# IR80-250GF.net
KiCad netlist of a schematic drawn in Altium Designer
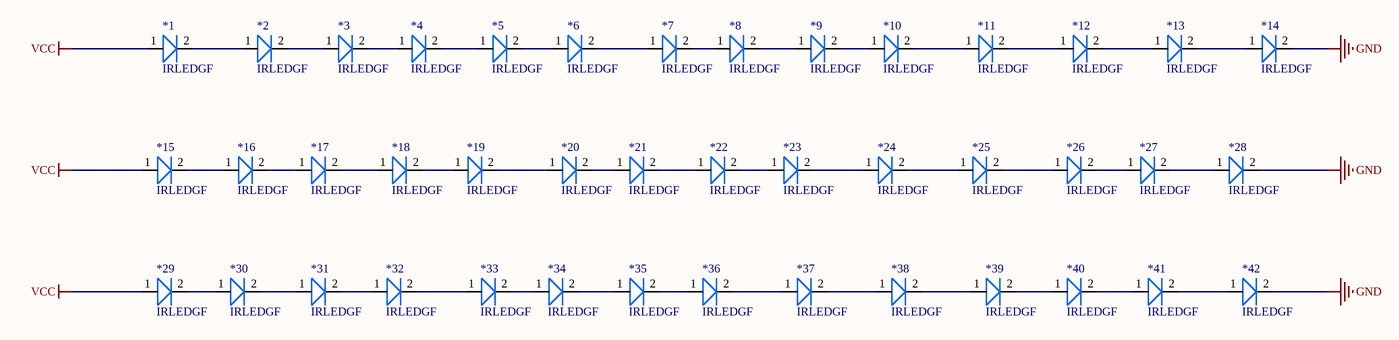
[diagram p0: IR80-250GF.SchDoc]

(export (version "E")
  (design (tool "Eeschema 10.0.6"))
  (components
    (comp (ref "*1")
      (value "IRLEDGF")
      (footprint "LED:LED 1W/3W")
      (libsource (lib "mySchLib") (part "IRLEDGF"))
    )
    (comp (ref "*2")
      (value "IRLEDGF")
      (footprint "LED:LED 1W/3W")
      (libsource (lib "mySchLib") (part "IRLEDGF"))
    )
    (comp (ref "*3")
      (value "IRLEDGF")
      (footprint "LED:LED 1W/3W")
      (libsource (lib "mySchLib") (part "IRLEDGF"))
    )
    (comp (ref "*4")
      (value "IRLEDGF")
      (footprint "LED:LED 1W/3W")
      (libsource (lib "mySchLib") (part "IRLEDGF"))
    )
    (comp (ref "*5")
      (value "IRLEDGF")
      (footprint "LED:LED 1W/3W")
      (libsource (lib "mySchLib") (part "IRLEDGF"))
    )
    (comp (ref "*6")
      (value "IRLEDGF")
      (footprint "LED:LED 1W/3W")
      (libsource (lib "mySchLib") (part "IRLEDGF"))
    )
    (comp (ref "*7")
      (value "IRLEDGF")
      (footprint "LED:LED 1W/3W")
      (libsource (lib "mySchLib") (part "IRLEDGF"))
    )
    (comp (ref "*8")
      (value "IRLEDGF")
      (footprint "LED:LED 1W/3W")
      (libsource (lib "mySchLib") (part "IRLEDGF"))
    )
    (comp (ref "*9")
      (value "IRLEDGF")
      (footprint "LED:LED 1W/3W")
      (libsource (lib "mySchLib") (part "IRLEDGF"))
    )
    (comp (ref "*10")
      (value "IRLEDGF")
      (footprint "LED:LED 1W/3W")
      (libsource (lib "mySchLib") (part "IRLEDGF"))
    )
    (comp (ref "*11")
      (value "IRLEDGF")
      (footprint "LED:LED 1W/3W")
      (libsource (lib "mySchLib") (part "IRLEDGF"))
    )
    (comp (ref "*12")
      (value "IRLEDGF")
      (footprint "LED:LED 1W/3W")
      (libsource (lib "mySchLib") (part "IRLEDGF"))
    )
    (comp (ref "*13")
      (value "IRLEDGF")
      (footprint "LED:LED 1W/3W")
      (libsource (lib "mySchLib") (part "IRLEDGF"))
    )
    (comp (ref "*14")
      (value "IRLEDGF")
      (footprint "LED:LED 1W/3W")
      (libsource (lib "mySchLib") (part "IRLEDGF"))
    )
    (comp (ref "*15")
      (value "IRLEDGF")
      (footprint "LED:LED 1W/3W")
      (libsource (lib "mySchLib") (part "IRLEDGF"))
    )
    (comp (ref "*16")
      (value "IRLEDGF")
      (footprint "LED:LED 1W/3W")
      (libsource (lib "mySchLib") (part "IRLEDGF"))
    )
    (comp (ref "*17")
      (value "IRLEDGF")
      (footprint "LED:LED 1W/3W")
      (libsource (lib "mySchLib") (part "IRLEDGF"))
    )
    (comp (ref "*18")
      (value "IRLEDGF")
      (footprint "LED:LED 1W/3W")
      (libsource (lib "mySchLib") (part "IRLEDGF"))
    )
    (comp (ref "*19")
      (value "IRLEDGF")
      (footprint "LED:LED 1W/3W")
      (libsource (lib "mySchLib") (part "IRLEDGF"))
    )
    (comp (ref "*20")
      (value "IRLEDGF")
      (footprint "LED:LED 1W/3W")
      (libsource (lib "mySchLib") (part "IRLEDGF"))
    )
    (comp (ref "*21")
      (value "IRLEDGF")
      (footprint "LED:LED 1W/3W")
      (libsource (lib "mySchLib") (part "IRLEDGF"))
    )
    (comp (ref "*22")
      (value "IRLEDGF")
      (footprint "LED:LED 1W/3W")
      (libsource (lib "mySchLib") (part "IRLEDGF"))
    )
    (comp (ref "*23")
      (value "IRLEDGF")
      (footprint "LED:LED 1W/3W")
      (libsource (lib "mySchLib") (part "IRLEDGF"))
    )
    (comp (ref "*24")
      (value "IRLEDGF")
      (footprint "LED:LED 1W/3W")
      (libsource (lib "mySchLib") (part "IRLEDGF"))
    )
    (comp (ref "*25")
      (value "IRLEDGF")
      (footprint "LED:LED 1W/3W")
      (libsource (lib "mySchLib") (part "IRLEDGF"))
    )
    (comp (ref "*26")
      (value "IRLEDGF")
      (footprint "LED:LED 1W/3W")
      (libsource (lib "mySchLib") (part "IRLEDGF"))
    )
    (comp (ref "*27")
      (value "IRLEDGF")
      (footprint "LED:LED 1W/3W")
      (libsource (lib "mySchLib") (part "IRLEDGF"))
    )
    (comp (ref "*28")
      (value "IRLEDGF")
      (footprint "LED:LED 1W/3W")
      (libsource (lib "mySchLib") (part "IRLEDGF"))
    )
    (comp (ref "*29")
      (value "IRLEDGF")
      (footprint "LED:LED 1W/3W")
      (libsource (lib "mySchLib") (part "IRLEDGF"))
    )
    (comp (ref "*30")
      (value "IRLEDGF")
      (footprint "LED:LED 1W/3W")
      (libsource (lib "mySchLib") (part "IRLEDGF"))
    )
    (comp (ref "*31")
      (value "IRLEDGF")
      (footprint "LED:LED 1W/3W")
      (libsource (lib "mySchLib") (part "IRLEDGF"))
    )
    (comp (ref "*32")
      (value "IRLEDGF")
      (footprint "LED:LED 1W/3W")
      (libsource (lib "mySchLib") (part "IRLEDGF"))
    )
    (comp (ref "*33")
      (value "IRLEDGF")
      (footprint "LED:LED 1W/3W")
      (libsource (lib "mySchLib") (part "IRLEDGF"))
    )
    (comp (ref "*34")
      (value "IRLEDGF")
      (footprint "LED:LED 1W/3W")
      (libsource (lib "mySchLib") (part "IRLEDGF"))
    )
    (comp (ref "*35")
      (value "IRLEDGF")
      (footprint "LED:LED 1W/3W")
      (libsource (lib "mySchLib") (part "IRLEDGF"))
    )
    (comp (ref "*36")
      (value "IRLEDGF")
      (footprint "LED:LED 1W/3W")
      (libsource (lib "mySchLib") (part "IRLEDGF"))
    )
    (comp (ref "*37")
      (value "IRLEDGF")
      (footprint "LED:LED 1W/3W")
      (libsource (lib "mySchLib") (part "IRLEDGF"))
    )
    (comp (ref "*38")
      (value "IRLEDGF")
      (footprint "LED:LED 1W/3W")
      (libsource (lib "mySchLib") (part "IRLEDGF"))
    )
    (comp (ref "*39")
      (value "IRLEDGF")
      (footprint "LED:LED 1W/3W")
      (libsource (lib "mySchLib") (part "IRLEDGF"))
    )
    (comp (ref "*40")
      (value "IRLEDGF")
      (footprint "LED:LED 1W/3W")
      (libsource (lib "mySchLib") (part "IRLEDGF"))
    )
    (comp (ref "*41")
      (value "IRLEDGF")
      (footprint "LED:LED 1W/3W")
      (libsource (lib "mySchLib") (part "IRLEDGF"))
    )
    (comp (ref "*42")
      (value "IRLEDGF")
      (footprint "LED:LED 1W/3W")
      (libsource (lib "mySchLib") (part "IRLEDGF"))
    )
  )
  (nets
    (net (code "1") (name "GND") (class "Default")
      (node (ref "*14") (pin "2") (pinfunction "-_2") (pintype "open_collector"))
      (node (ref "*28") (pin "2") (pinfunction "-_2") (pintype "open_collector"))
      (node (ref "*42") (pin "2") (pinfunction "-_2") (pintype "open_collector"))
    )
    (net (code "2") (name "Net-(*1--)") (class "Default")
      (node (ref "*1") (pin "2") (pinfunction "-_2") (pintype "open_collector"))
      (node (ref "*2") (pin "1") (pinfunction "+_1") (pintype "passive"))
    )
    (net (code "3") (name "Net-(*2--)") (class "Default")
      (node (ref "*2") (pin "2") (pinfunction "-_2") (pintype "open_collector"))
      (node (ref "*3") (pin "1") (pinfunction "+_1") (pintype "passive"))
    )
    (net (code "4") (name "Net-(*3--)") (class "Default")
      (node (ref "*3") (pin "2") (pinfunction "-_2") (pintype "open_collector"))
      (node (ref "*4") (pin "1") (pinfunction "+_1") (pintype "passive"))
    )
    (net (code "5") (name "Net-(*4--)") (class "Default")
      (node (ref "*4") (pin "2") (pinfunction "-_2") (pintype "open_collector"))
      (node (ref "*5") (pin "1") (pinfunction "+_1") (pintype "passive"))
    )
    (net (code "6") (name "Net-(*5--)") (class "Default")
      (node (ref "*5") (pin "2") (pinfunction "-_2") (pintype "open_collector"))
      (node (ref "*6") (pin "1") (pinfunction "+_1") (pintype "passive"))
    )
    (net (code "7") (name "Net-(*6--)") (class "Default")
      (node (ref "*6") (pin "2") (pinfunction "-_2") (pintype "open_collector"))
      (node (ref "*7") (pin "1") (pinfunction "+_1") (pintype "passive"))
    )
    (net (code "8") (name "Net-(*7--)") (class "Default")
      (node (ref "*7") (pin "2") (pinfunction "-_2") (pintype "open_collector"))
      (node (ref "*8") (pin "1") (pinfunction "+_1") (pintype "passive"))
    )
    (net (code "9") (name "Net-(*8--)") (class "Default")
      (node (ref "*8") (pin "2") (pinfunction "-_2") (pintype "open_collector"))
      (node (ref "*9") (pin "1") (pinfunction "+_1") (pintype "passive"))
    )
    (net (code "10") (name "Net-(*10-+)") (class "Default")
      (node (ref "*10") (pin "1") (pinfunction "+_1") (pintype "passive"))
      (node (ref "*9") (pin "2") (pinfunction "-_2") (pintype "open_collector"))
    )
    (net (code "11") (name "Net-(*10--)") (class "Default")
      (node (ref "*10") (pin "2") (pinfunction "-_2") (pintype "open_collector"))
      (node (ref "*11") (pin "1") (pinfunction "+_1") (pintype "passive"))
    )
    (net (code "12") (name "Net-(*11--)") (class "Default")
      (node (ref "*11") (pin "2") (pinfunction "-_2") (pintype "open_collector"))
      (node (ref "*12") (pin "1") (pinfunction "+_1") (pintype "passive"))
    )
    (net (code "13") (name "Net-(*12--)") (class "Default")
      (node (ref "*12") (pin "2") (pinfunction "-_2") (pintype "open_collector"))
      (node (ref "*13") (pin "1") (pinfunction "+_1") (pintype "passive"))
    )
    (net (code "14") (name "Net-(*13--)") (class "Default")
      (node (ref "*13") (pin "2") (pinfunction "-_2") (pintype "open_collector"))
      (node (ref "*14") (pin "1") (pinfunction "+_1") (pintype "passive"))
    )
    (net (code "15") (name "Net-(*15--)") (class "Default")
      (node (ref "*15") (pin "2") (pinfunction "-_2") (pintype "open_collector"))
      (node (ref "*16") (pin "1") (pinfunction "+_1") (pintype "passive"))
    )
    (net (code "16") (name "Net-(*16--)") (class "Default")
      (node (ref "*16") (pin "2") (pinfunction "-_2") (pintype "open_collector"))
      (node (ref "*17") (pin "1") (pinfunction "+_1") (pintype "passive"))
    )
    (net (code "17") (name "Net-(*17--)") (class "Default")
      (node (ref "*17") (pin "2") (pinfunction "-_2") (pintype "open_collector"))
      (node (ref "*18") (pin "1") (pinfunction "+_1") (pintype "passive"))
    )
    (net (code "18") (name "Net-(*18--)") (class "Default")
      (node (ref "*18") (pin "2") (pinfunction "-_2") (pintype "open_collector"))
      (node (ref "*19") (pin "1") (pinfunction "+_1") (pintype "passive"))
    )
    (net (code "19") (name "Net-(*19--)") (class "Default")
      (node (ref "*19") (pin "2") (pinfunction "-_2") (pintype "open_collector"))
      (node (ref "*20") (pin "1") (pinfunction "+_1") (pintype "passive"))
    )
    (net (code "20") (name "Net-(*20--)") (class "Default")
      (node (ref "*20") (pin "2") (pinfunction "-_2") (pintype "open_collector"))
      (node (ref "*21") (pin "1") (pinfunction "+_1") (pintype "passive"))
    )
    (net (code "21") (name "Net-(*21--)") (class "Default")
      (node (ref "*21") (pin "2") (pinfunction "-_2") (pintype "open_collector"))
      (node (ref "*22") (pin "1") (pinfunction "+_1") (pintype "passive"))
    )
    (net (code "22") (name "Net-(*22--)") (class "Default")
      (node (ref "*22") (pin "2") (pinfunction "-_2") (pintype "open_collector"))
      (node (ref "*23") (pin "1") (pinfunction "+_1") (pintype "passive"))
    )
    (net (code "23") (name "Net-(*23--)") (class "Default")
      (node (ref "*23") (pin "2") (pinfunction "-_2") (pintype "open_collector"))
      (node (ref "*24") (pin "1") (pinfunction "+_1") (pintype "passive"))
    )
    (net (code "24") (name "Net-(*24--)") (class "Default")
      (node (ref "*24") (pin "2") (pinfunction "-_2") (pintype "open_collector"))
      (node (ref "*25") (pin "1") (pinfunction "+_1") (pintype "passive"))
    )
    (net (code "25") (name "Net-(*25--)") (class "Default")
      (node (ref "*25") (pin "2") (pinfunction "-_2") (pintype "open_collector"))
      (node (ref "*26") (pin "1") (pinfunction "+_1") (pintype "passive"))
    )
    (net (code "26") (name "Net-(*26--)") (class "Default")
      (node (ref "*26") (pin "2") (pinfunction "-_2") (pintype "open_collector"))
      (node (ref "*27") (pin "1") (pinfunction "+_1") (pintype "passive"))
    )
    (net (code "27") (name "Net-(*27--)") (class "Default")
      (node (ref "*27") (pin "2") (pinfunction "-_2") (pintype "open_collector"))
      (node (ref "*28") (pin "1") (pinfunction "+_1") (pintype "passive"))
    )
    (net (code "28") (name "Net-(*29--)") (class "Default")
      (node (ref "*29") (pin "2") (pinfunction "-_2") (pintype "open_collector"))
      (node (ref "*30") (pin "1") (pinfunction "+_1") (pintype "passive"))
    )
    (net (code "29") (name "Net-(*30--)") (class "Default")
      (node (ref "*30") (pin "2") (pinfunction "-_2") (pintype "open_collector"))
      (node (ref "*31") (pin "1") (pinfunction "+_1") (pintype "passive"))
    )
    (net (code "30") (name "Net-(*31--)") (class "Default")
      (node (ref "*31") (pin "2") (pinfunction "-_2") (pintype "open_collector"))
      (node (ref "*32") (pin "1") (pinfunction "+_1") (pintype "passive"))
    )
    (net (code "31") (name "Net-(*32--)") (class "Default")
      (node (ref "*32") (pin "2") (pinfunction "-_2") (pintype "open_collector"))
      (node (ref "*33") (pin "1") (pinfunction "+_1") (pintype "passive"))
    )
    (net (code "32") (name "Net-(*33--)") (class "Default")
      (node (ref "*33") (pin "2") (pinfunction "-_2") (pintype "open_collector"))
      (node (ref "*34") (pin "1") (pinfunction "+_1") (pintype "passive"))
    )
    (net (code "33") (name "Net-(*34--)") (class "Default")
      (node (ref "*34") (pin "2") (pinfunction "-_2") (pintype "open_collector"))
      (node (ref "*35") (pin "1") (pinfunction "+_1") (pintype "passive"))
    )
    (net (code "34") (name "Net-(*35--)") (class "Default")
      (node (ref "*35") (pin "2") (pinfunction "-_2") (pintype "open_collector"))
      (node (ref "*36") (pin "1") (pinfunction "+_1") (pintype "passive"))
    )
    (net (code "35") (name "Net-(*36--)") (class "Default")
      (node (ref "*36") (pin "2") (pinfunction "-_2") (pintype "open_collector"))
      (node (ref "*37") (pin "1") (pinfunction "+_1") (pintype "passive"))
    )
    (net (code "36") (name "Net-(*37--)") (class "Default")
      (node (ref "*37") (pin "2") (pinfunction "-_2") (pintype "open_collector"))
      (node (ref "*38") (pin "1") (pinfunction "+_1") (pintype "passive"))
    )
    (net (code "37") (name "Net-(*38--)") (class "Default")
      (node (ref "*38") (pin "2") (pinfunction "-_2") (pintype "open_collector"))
      (node (ref "*39") (pin "1") (pinfunction "+_1") (pintype "passive"))
    )
    (net (code "38") (name "Net-(*39--)") (class "Default")
      (node (ref "*39") (pin "2") (pinfunction "-_2") (pintype "open_collector"))
      (node (ref "*40") (pin "1") (pinfunction "+_1") (pintype "passive"))
    )
    (net (code "39") (name "Net-(*40--)") (class "Default")
      (node (ref "*40") (pin "2") (pinfunction "-_2") (pintype "open_collector"))
      (node (ref "*41") (pin "1") (pinfunction "+_1") (pintype "passive"))
    )
    (net (code "40") (name "Net-(*41--)") (class "Default")
      (node (ref "*41") (pin "2") (pinfunction "-_2") (pintype "open_collector"))
      (node (ref "*42") (pin "1") (pinfunction "+_1") (pintype "passive"))
    )
    (net (code "41") (name "VCC") (class "Default")
      (node (ref "*1") (pin "1") (pinfunction "+_1") (pintype "passive"))
      (node (ref "*15") (pin "1") (pinfunction "+_1") (pintype "passive"))
      (node (ref "*29") (pin "1") (pinfunction "+_1") (pintype "passive"))
    )
  )
)
